# STSPIN32F0A_ESC4.net
KiCad netlist of a schematic drawn in Altium Designer
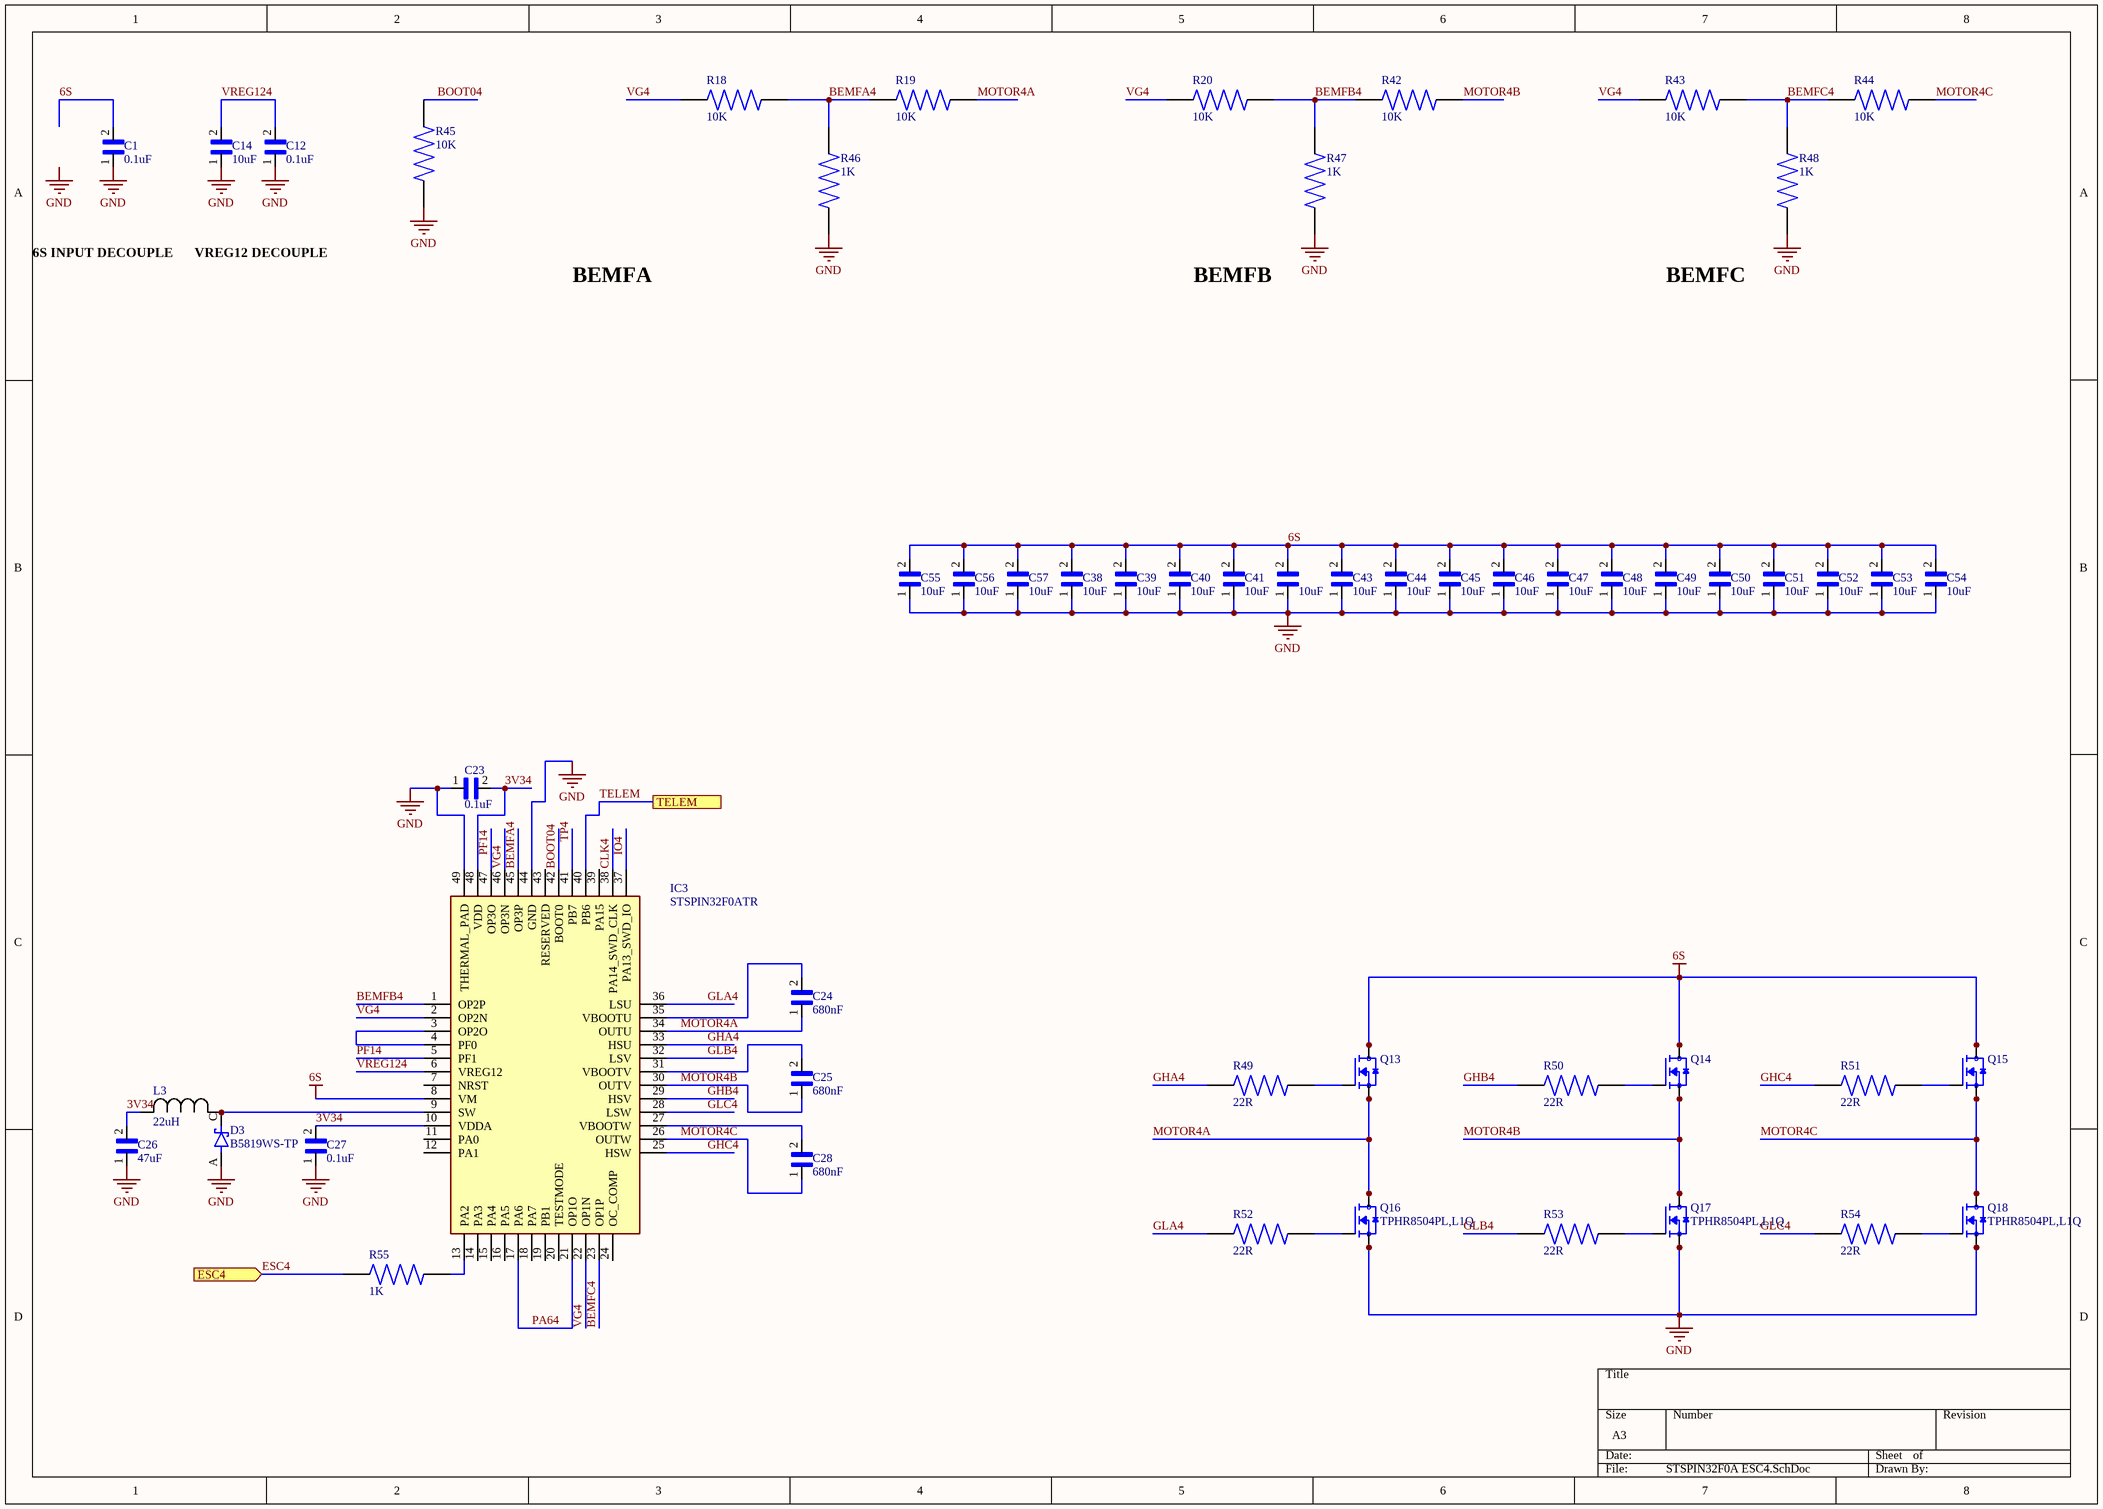
[diagram p0: STSPIN32F0A ESC4.SchDoc]

(export (version "E")
  (design (tool "Eeschema 10.0.6"))
  (components
    (comp (ref "C1")
      (value "0.1uF")
      (footprint "CAPC1005X55N")
      (fields (field (name "MP") "GRM1555C1H222JA01D"))
      (libsource (lib "GRM1555C1H222JA01D") (part "GRM1555C1H222JA01D"))
    )
    (comp (ref "C12")
      (value "0.1uF")
      (footprint "CAPC1005X55N")
      (fields (field (name "MP") "GRM1555C1H222JA01D"))
      (libsource (lib "GRM1555C1H222JA01D") (part "GRM1555C1H222JA01D"))
    )
    (comp (ref "C14")
      (value "10uF")
      (footprint "CAPC1608X90N")
      (description "SMD Capacitor X7R(EIA) with Capacitance: 0.22uF Tol. 5%. Rated Voltage: 25Vdc")
      (fields (field (name "MP") "GRM188R71E224JA88D"))
      (libsource (lib "GRM188R71E224JA88D") (part "GRM188R71E224JA88D"))
    )
    (comp (ref "C23")
      (value "0.1uF")
      (footprint "CAPC1005X55N")
      (fields (field (name "MP") "GRM1555C1H222JA01D"))
      (libsource (lib "") (part "GRM1555C1H222JA01D_1"))
    )
    (comp (ref "C24")
      (value "680nF")
      (footprint "CAPC1005X55N")
      (fields (field (name "MP") "GRM1555C1H222JA01D"))
      (libsource (lib "GRM1555C1H222JA01D") (part "GRM1555C1H222JA01D"))
    )
    (comp (ref "C25")
      (value "680nF")
      (footprint "CAPC1005X55N")
      (fields (field (name "MP") "GRM1555C1H222JA01D"))
      (libsource (lib "GRM1555C1H222JA01D") (part "GRM1555C1H222JA01D"))
    )
    (comp (ref "C26")
      (value "47uF")
      (footprint "CAPC1608X90N")
      (description "SMD Capacitor X7R(EIA) with Capacitance: 0.22uF Tol. 5%. Rated Voltage: 25Vdc")
      (fields (field (name "MP") "GRM188R71E224JA88D"))
      (libsource (lib "GRM188R71E224JA88D") (part "GRM188R71E224JA88D"))
    )
    (comp (ref "C27")
      (value "0.1uF")
      (footprint "CAPC1005X55N")
      (fields (field (name "MP") "GRM1555C1H222JA01D"))
      (libsource (lib "GRM1555C1H222JA01D") (part "GRM1555C1H222JA01D"))
    )
    (comp (ref "C28")
      (value "680nF")
      (footprint "CAPC1005X55N")
      (fields (field (name "MP") "GRM1555C1H222JA01D"))
      (libsource (lib "GRM1555C1H222JA01D") (part "GRM1555C1H222JA01D"))
    )
    (comp (ref "C38")
      (value "10uF")
      (footprint "CAPC3216X190N")
      (description "Ceramic Capacitor")
      (fields (field (name "MP") "GRM31CC80G227ME11K"))
      (libsource (lib "GRM31CC80G227ME11K") (part "GRM31CC80G227ME11K"))
    )
    (comp (ref "C39")
      (value "10uF")
      (footprint "CAPC3216X190N")
      (description "Ceramic Capacitor")
      (fields (field (name "MP") "GRM31CC80G227ME11K"))
      (libsource (lib "GRM31CC80G227ME11K") (part "GRM31CC80G227ME11K"))
    )
    (comp (ref "C40")
      (value "10uF")
      (footprint "CAPC3216X190N")
      (description "Ceramic Capacitor")
      (fields (field (name "MP") "GRM31CC80G227ME11K"))
      (libsource (lib "GRM31CC80G227ME11K") (part "GRM31CC80G227ME11K"))
    )
    (comp (ref "C41")
      (value "10uF")
      (footprint "CAPC3216X190N")
      (description "Ceramic Capacitor")
      (fields (field (name "MP") "GRM31CC80G227ME11K"))
      (libsource (lib "GRM31CC80G227ME11K") (part "GRM31CC80G227ME11K"))
    )
    (comp (ref "C42")
      (value "10uF")
      (footprint "CAPC3216X190N")
      (description "Ceramic Capacitor")
      (fields (field (name "MP") "GRM31CC80G227ME11K"))
      (libsource (lib "GRM31CC80G227ME11K") (part "GRM31CC80G227ME11K"))
    )
    (comp (ref "C43")
      (value "10uF")
      (footprint "CAPC3216X190N")
      (description "Ceramic Capacitor")
      (fields (field (name "MP") "GRM31CC80G227ME11K"))
      (libsource (lib "GRM31CC80G227ME11K") (part "GRM31CC80G227ME11K"))
    )
    (comp (ref "C44")
      (value "10uF")
      (footprint "CAPC3216X190N")
      (description "Ceramic Capacitor")
      (fields (field (name "MP") "GRM31CC80G227ME11K"))
      (libsource (lib "GRM31CC80G227ME11K") (part "GRM31CC80G227ME11K"))
    )
    (comp (ref "C45")
      (value "10uF")
      (footprint "CAPC3216X190N")
      (description "Ceramic Capacitor")
      (fields (field (name "MP") "GRM31CC80G227ME11K"))
      (libsource (lib "GRM31CC80G227ME11K") (part "GRM31CC80G227ME11K"))
    )
    (comp (ref "C46")
      (value "10uF")
      (footprint "CAPC3216X190N")
      (description "Ceramic Capacitor")
      (fields (field (name "MP") "GRM31CC80G227ME11K"))
      (libsource (lib "GRM31CC80G227ME11K") (part "GRM31CC80G227ME11K"))
    )
    (comp (ref "C47")
      (value "10uF")
      (footprint "CAPC3216X190N")
      (description "Ceramic Capacitor")
      (fields (field (name "MP") "GRM31CC80G227ME11K"))
      (libsource (lib "GRM31CC80G227ME11K") (part "GRM31CC80G227ME11K"))
    )
    (comp (ref "C48")
      (value "10uF")
      (footprint "CAPC3216X190N")
      (description "Ceramic Capacitor")
      (fields (field (name "MP") "GRM31CC80G227ME11K"))
      (libsource (lib "GRM31CC80G227ME11K") (part "GRM31CC80G227ME11K"))
    )
    (comp (ref "C49")
      (value "10uF")
      (footprint "CAPC3216X190N")
      (description "Ceramic Capacitor")
      (fields (field (name "MP") "GRM31CC80G227ME11K"))
      (libsource (lib "GRM31CC80G227ME11K") (part "GRM31CC80G227ME11K"))
    )
    (comp (ref "C50")
      (value "10uF")
      (footprint "CAPC3216X190N")
      (description "Ceramic Capacitor")
      (fields (field (name "MP") "GRM31CC80G227ME11K"))
      (libsource (lib "GRM31CC80G227ME11K") (part "GRM31CC80G227ME11K"))
    )
    (comp (ref "C51")
      (value "10uF")
      (footprint "CAPC3216X190N")
      (description "Ceramic Capacitor")
      (fields (field (name "MP") "GRM31CC80G227ME11K"))
      (libsource (lib "GRM31CC80G227ME11K") (part "GRM31CC80G227ME11K"))
    )
    (comp (ref "C52")
      (value "10uF")
      (footprint "CAPC3216X190N")
      (description "Ceramic Capacitor")
      (fields (field (name "MP") "GRM31CC80G227ME11K"))
      (libsource (lib "GRM31CC80G227ME11K") (part "GRM31CC80G227ME11K"))
    )
    (comp (ref "C53")
      (value "10uF")
      (footprint "CAPC3216X190N")
      (description "Ceramic Capacitor")
      (fields (field (name "MP") "GRM31CC80G227ME11K"))
      (libsource (lib "GRM31CC80G227ME11K") (part "GRM31CC80G227ME11K"))
    )
    (comp (ref "C54")
      (value "10uF")
      (footprint "CAPC3216X190N")
      (description "Ceramic Capacitor")
      (fields (field (name "MP") "GRM31CC80G227ME11K"))
      (libsource (lib "GRM31CC80G227ME11K") (part "GRM31CC80G227ME11K"))
    )
    (comp (ref "C55")
      (value "10uF")
      (footprint "CAPC3216X190N")
      (description "Ceramic Capacitor")
      (fields (field (name "MP") "GRM31CC80G227ME11K"))
      (libsource (lib "GRM31CC80G227ME11K") (part "GRM31CC80G227ME11K"))
    )
    (comp (ref "C56")
      (value "10uF")
      (footprint "CAPC3216X190N")
      (description "Ceramic Capacitor")
      (fields (field (name "MP") "GRM31CC80G227ME11K"))
      (libsource (lib "GRM31CC80G227ME11K") (part "GRM31CC80G227ME11K"))
    )
    (comp (ref "C57")
      (value "10uF")
      (footprint "CAPC3216X190N")
      (description "Ceramic Capacitor")
      (fields (field (name "MP") "GRM31CC80G227ME11K"))
      (libsource (lib "GRM31CC80G227ME11K") (part "GRM31CC80G227ME11K"))
    )
    (comp (ref "D3")
      (value "B5819WS-TP")
      (footprint "SOD2512X115N")
      (fields (field (name "MF") "{'manufacturer': u'Micro Commercial Components'}"))
      (libsource (lib "SnapEDA_Library") (part "B5819WS-TP"))
    )
    (comp (ref "IC3")
      (value "STSPIN32F0ATR")
      (footprint "SamacSys:QFN50P700X700X100-49N-D")
      (description "Integrated Circuit")
      (fields (field (name "MOUSER PART NUMBER") "511-STSPIN32F0ATR"))
      (libsource (lib "SamacSys") (part "STSPIN32F0ATR"))
    )
    (comp (ref "L3")
      (value "22uH")
      (footprint "IND_BOURNS_SRN3015")
      (description "No Description Available")
      (fields
        (field (name "MANUFACTURER_PART_NUMBER") "SRN3015-220M")
        (field (name "COPYRIGHT") "Copyright (C) 2022 Ultra Librarian. All rights reserved.")
      )
      (libsource (lib "SRN3015-220M") (part "SRN3015-220M"))
    )
    (comp (ref "Q13")
      (value "TPHR8504PL,L1Q")
      (footprint "TRANS_TPHR8504PL,L1Q")
      (description "N-Channel 40V 150A (Tc) 1W (Ta), 170W (Tc) Surface Mount 8-SOP Advance (5x5)")
      (fields (field (name "MF") "Toshiba Semiconductor"))
      (libsource (lib "TPHR8504PL_L1Q") (part "TPHR8504PL,L1Q"))
    )
    (comp (ref "Q14")
      (value "TPHR8504PL,L1Q")
      (footprint "TRANS_TPHR8504PL,L1Q")
      (description "N-Channel 40V 150A (Tc) 1W (Ta), 170W (Tc) Surface Mount 8-SOP Advance (5x5)")
      (fields (field (name "MF") "Toshiba Semiconductor"))
      (libsource (lib "TPHR8504PL_L1Q") (part "TPHR8504PL,L1Q"))
    )
    (comp (ref "Q15")
      (value "TPHR8504PL,L1Q")
      (footprint "TRANS_TPHR8504PL,L1Q")
      (description "N-Channel 40V 150A (Tc) 1W (Ta), 170W (Tc) Surface Mount 8-SOP Advance (5x5)")
      (fields (field (name "MF") "Toshiba Semiconductor"))
      (libsource (lib "TPHR8504PL_L1Q") (part "TPHR8504PL,L1Q"))
    )
    (comp (ref "Q16")
      (value "TPHR8504PL,L1Q")
      (footprint "TRANS_TPHR8504PL,L1Q")
      (description "N-Channel 40V 150A (Tc) 1W (Ta), 170W (Tc) Surface Mount 8-SOP Advance (5x5)")
      (fields (field (name "MF") "Toshiba Semiconductor"))
      (libsource (lib "TPHR8504PL_L1Q") (part "TPHR8504PL,L1Q"))
    )
    (comp (ref "Q17")
      (value "TPHR8504PL,L1Q")
      (footprint "TRANS_TPHR8504PL,L1Q")
      (description "N-Channel 40V 150A (Tc) 1W (Ta), 170W (Tc) Surface Mount 8-SOP Advance (5x5)")
      (fields (field (name "MF") "Toshiba Semiconductor"))
      (libsource (lib "TPHR8504PL_L1Q") (part "TPHR8504PL,L1Q"))
    )
    (comp (ref "Q18")
      (value "TPHR8504PL,L1Q")
      (footprint "TRANS_TPHR8504PL,L1Q")
      (description "N-Channel 40V 150A (Tc) 1W (Ta), 170W (Tc) Surface Mount 8-SOP Advance (5x5)")
      (fields (field (name "MF") "Toshiba Semiconductor"))
      (libsource (lib "TPHR8504PL_L1Q") (part "TPHR8504PL,L1Q"))
    )
    (comp (ref "R18")
      (value "10K")
      (footprint "RESC1005X37N")
      (fields (field (name "MP") "RE0402BRE07330KL") (field (name "MF") "{'manufacturer': u'Yageo'}"))
      (libsource (lib "SnapEDA_Library") (part "RE0402BRE07330KL"))
    )
    (comp (ref "R19")
      (value "10K")
      (footprint "RESC1005X37N")
      (fields (field (name "MP") "RE0402BRE07330KL") (field (name "MF") "{'manufacturer': u'Yageo'}"))
      (libsource (lib "SnapEDA_Library") (part "RE0402BRE07330KL"))
    )
    (comp (ref "R20")
      (value "10K")
      (footprint "RESC1005X37N")
      (fields (field (name "MP") "RE0402BRE07330KL") (field (name "MF") "{'manufacturer': u'Yageo'}"))
      (libsource (lib "SnapEDA_Library") (part "RE0402BRE07330KL"))
    )
    (comp (ref "R42")
      (value "10K")
      (footprint "RESC1005X37N")
      (fields (field (name "MP") "RE0402BRE07330KL") (field (name "MF") "{'manufacturer': u'Yageo'}"))
      (libsource (lib "SnapEDA_Library") (part "RE0402BRE07330KL"))
    )
    (comp (ref "R43")
      (value "10K")
      (footprint "RESC1005X37N")
      (fields (field (name "MP") "RE0402BRE07330KL") (field (name "MF") "{'manufacturer': u'Yageo'}"))
      (libsource (lib "SnapEDA_Library") (part "RE0402BRE07330KL"))
    )
    (comp (ref "R44")
      (value "10K")
      (footprint "RESC1005X37N")
      (fields (field (name "MP") "RE0402BRE07330KL") (field (name "MF") "{'manufacturer': u'Yageo'}"))
      (libsource (lib "SnapEDA_Library") (part "RE0402BRE07330KL"))
    )
    (comp (ref "R45")
      (value "10K")
      (footprint "RESC1005X37N")
      (fields (field (name "MP") "RE0402BRE07330KL") (field (name "MF") "{'manufacturer': u'Yageo'}"))
      (libsource (lib "SnapEDA_Library") (part "RE0402BRE07330KL"))
    )
    (comp (ref "R46")
      (value "1K")
      (footprint "RESC1005X37N")
      (fields (field (name "MP") "RE0402BRE07330KL") (field (name "MF") "{'manufacturer': u'Yageo'}"))
      (libsource (lib "SnapEDA_Library") (part "RE0402BRE07330KL"))
    )
    (comp (ref "R47")
      (value "1K")
      (footprint "RESC1005X37N")
      (fields (field (name "MP") "RE0402BRE07330KL") (field (name "MF") "{'manufacturer': u'Yageo'}"))
      (libsource (lib "SnapEDA_Library") (part "RE0402BRE07330KL"))
    )
    (comp (ref "R48")
      (value "1K")
      (footprint "RESC1005X37N")
      (fields (field (name "MP") "RE0402BRE07330KL") (field (name "MF") "{'manufacturer': u'Yageo'}"))
      (libsource (lib "SnapEDA_Library") (part "RE0402BRE07330KL"))
    )
    (comp (ref "R49")
      (value "22R")
      (footprint "RESC1005X37N")
      (fields (field (name "MP") "RE0402BRE07330KL") (field (name "MF") "{'manufacturer': u'Yageo'}"))
      (libsource (lib "SnapEDA_Library") (part "RE0402BRE07330KL"))
    )
    (comp (ref "R50")
      (value "22R")
      (footprint "RESC1005X37N")
      (fields (field (name "MP") "RE0402BRE07330KL") (field (name "MF") "{'manufacturer': u'Yageo'}"))
      (libsource (lib "SnapEDA_Library") (part "RE0402BRE07330KL"))
    )
    (comp (ref "R51")
      (value "22R")
      (footprint "RESC1005X37N")
      (fields (field (name "MP") "RE0402BRE07330KL") (field (name "MF") "{'manufacturer': u'Yageo'}"))
      (libsource (lib "SnapEDA_Library") (part "RE0402BRE07330KL"))
    )
    (comp (ref "R52")
      (value "22R")
      (footprint "RESC1005X37N")
      (fields (field (name "MP") "RE0402BRE07330KL") (field (name "MF") "{'manufacturer': u'Yageo'}"))
      (libsource (lib "SnapEDA_Library") (part "RE0402BRE07330KL"))
    )
    (comp (ref "R53")
      (value "22R")
      (footprint "RESC1005X37N")
      (fields (field (name "MP") "RE0402BRE07330KL") (field (name "MF") "{'manufacturer': u'Yageo'}"))
      (libsource (lib "SnapEDA_Library") (part "RE0402BRE07330KL"))
    )
    (comp (ref "R54")
      (value "22R")
      (footprint "RESC1005X37N")
      (fields (field (name "MP") "RE0402BRE07330KL") (field (name "MF") "{'manufacturer': u'Yageo'}"))
      (libsource (lib "SnapEDA_Library") (part "RE0402BRE07330KL"))
    )
    (comp (ref "R55")
      (value "1K")
      (footprint "RESC1005X37N")
      (fields (field (name "MP") "RE0402BRE07330KL") (field (name "MF") "{'manufacturer': u'Yageo'}"))
      (libsource (lib "SnapEDA_Library") (part "RE0402BRE07330KL"))
    )
  )
  (nets
    (net (code "1") (name "/3V34") (class "Default")
      (node (ref "C23") (pin "2") (pinfunction "2_2") (pintype "passive"))
      (node (ref "C26") (pin "2") (pinfunction "2_2") (pintype "passive"))
      (node (ref "C27") (pin "2") (pinfunction "2_2") (pintype "passive"))
      (node (ref "IC3") (pin "10") (pinfunction "VDDA_10") (pintype "passive"))
      (node (ref "IC3") (pin "48") (pinfunction "VDD_48") (pintype "passive"))
      (node (ref "L3") (pin "2") (pinfunction "2_2") (pintype "passive"))
    )
    (net (code "2") (name "/BEMFA4") (class "Default")
      (node (ref "IC3") (pin "45") (pinfunction "OP3P_45") (pintype "passive"))
      (node (ref "R18") (pin "1") (pinfunction "1_1") (pintype "passive"))
      (node (ref "R19") (pin "2") (pinfunction "2_2") (pintype "passive"))
      (node (ref "R46") (pin "1") (pinfunction "1_1") (pintype "passive"))
    )
    (net (code "3") (name "/BEMFB4") (class "Default")
      (node (ref "IC3") (pin "1") (pinfunction "OP2P_1") (pintype "passive"))
      (node (ref "R20") (pin "1") (pinfunction "1_1") (pintype "passive"))
      (node (ref "R42") (pin "2") (pinfunction "2_2") (pintype "passive"))
      (node (ref "R47") (pin "1") (pinfunction "1_1") (pintype "passive"))
    )
    (net (code "4") (name "/BEMFC4") (class "Default")
      (node (ref "IC3") (pin "23") (pinfunction "OP1P_23") (pintype "passive"))
      (node (ref "R43") (pin "1") (pinfunction "1_1") (pintype "passive"))
      (node (ref "R44") (pin "2") (pinfunction "2_2") (pintype "passive"))
      (node (ref "R48") (pin "1") (pinfunction "1_1") (pintype "passive"))
    )
    (net (code "5") (name "/BOOT04") (class "Default")
      (node (ref "IC3") (pin "42") (pinfunction "BOOT0_42") (pintype "passive"))
      (node (ref "R45") (pin "2") (pinfunction "2_2") (pintype "passive"))
    )
    (net (code "6") (name "/CLK4") (class "Default")
      (node (ref "IC3") (pin "38") (pinfunction "PA14_SWD_CLK_38") (pintype "passive"))
    )
    (net (code "7") (name "/ESC4") (class "Default")
      (node (ref "R55") (pin "1") (pinfunction "1_1") (pintype "passive"))
    )
    (net (code "8") (name "/GHA4") (class "Default")
      (node (ref "IC3") (pin "33") (pinfunction "HSU_33") (pintype "passive"))
      (node (ref "R49") (pin "2") (pinfunction "2_2") (pintype "passive"))
    )
    (net (code "9") (name "/GHB4") (class "Default")
      (node (ref "IC3") (pin "29") (pinfunction "HSV_29") (pintype "passive"))
      (node (ref "R50") (pin "2") (pinfunction "2_2") (pintype "passive"))
    )
    (net (code "10") (name "/GHC4") (class "Default")
      (node (ref "IC3") (pin "25") (pinfunction "HSW_25") (pintype "passive"))
      (node (ref "R51") (pin "2") (pinfunction "2_2") (pintype "passive"))
    )
    (net (code "11") (name "/GLA4") (class "Default")
      (node (ref "IC3") (pin "36") (pinfunction "LSU_36") (pintype "passive"))
      (node (ref "R52") (pin "2") (pinfunction "2_2") (pintype "passive"))
    )
    (net (code "12") (name "/GLB4") (class "Default")
      (node (ref "IC3") (pin "32") (pinfunction "LSV_32") (pintype "passive"))
      (node (ref "R53") (pin "2") (pinfunction "2_2") (pintype "passive"))
    )
    (net (code "13") (name "/GLC4") (class "Default")
      (node (ref "IC3") (pin "28") (pinfunction "LSW_28") (pintype "passive"))
      (node (ref "R54") (pin "2") (pinfunction "2_2") (pintype "passive"))
    )
    (net (code "14") (name "/IO4") (class "Default")
      (node (ref "IC3") (pin "37") (pinfunction "PA13_SWD_IO_37") (pintype "passive"))
    )
    (net (code "15") (name "/MOTOR4A") (class "Default")
      (node (ref "C24") (pin "1") (pinfunction "1_1") (pintype "passive"))
      (node (ref "IC3") (pin "34") (pinfunction "OUTU_34") (pintype "passive"))
      (node (ref "Q13") (pin "1") (pinfunction "S_1") (pintype "passive"))
      (node (ref "Q13") (pin "2") (pinfunction "S_2") (pintype "passive"))
      (node (ref "Q13") (pin "3") (pinfunction "S_3") (pintype "passive"))
      (node (ref "Q16") (pin "5") (pinfunction "D_5") (pintype "passive"))
      (node (ref "Q16") (pin "6") (pinfunction "D_6") (pintype "passive"))
      (node (ref "Q16") (pin "7") (pinfunction "D_7") (pintype "passive"))
      (node (ref "Q16") (pin "8") (pinfunction "D_8") (pintype "passive"))
      (node (ref "Q16") (pin "9") (pinfunction "D_9") (pintype "passive"))
      (node (ref "R19") (pin "1") (pinfunction "1_1") (pintype "passive"))
    )
    (net (code "16") (name "/MOTOR4B") (class "Default")
      (node (ref "C25") (pin "1") (pinfunction "1_1") (pintype "passive"))
      (node (ref "IC3") (pin "30") (pinfunction "OUTV_30") (pintype "passive"))
      (node (ref "Q14") (pin "1") (pinfunction "S_1") (pintype "passive"))
      (node (ref "Q14") (pin "2") (pinfunction "S_2") (pintype "passive"))
      (node (ref "Q14") (pin "3") (pinfunction "S_3") (pintype "passive"))
      (node (ref "Q17") (pin "5") (pinfunction "D_5") (pintype "passive"))
      (node (ref "Q17") (pin "6") (pinfunction "D_6") (pintype "passive"))
      (node (ref "Q17") (pin "7") (pinfunction "D_7") (pintype "passive"))
      (node (ref "Q17") (pin "8") (pinfunction "D_8") (pintype "passive"))
      (node (ref "Q17") (pin "9") (pinfunction "D_9") (pintype "passive"))
      (node (ref "R42") (pin "1") (pinfunction "1_1") (pintype "passive"))
    )
    (net (code "17") (name "/MOTOR4C") (class "Default")
      (node (ref "C28") (pin "1") (pinfunction "1_1") (pintype "passive"))
      (node (ref "IC3") (pin "26") (pinfunction "OUTW_26") (pintype "passive"))
      (node (ref "Q15") (pin "1") (pinfunction "S_1") (pintype "passive"))
      (node (ref "Q15") (pin "2") (pinfunction "S_2") (pintype "passive"))
      (node (ref "Q15") (pin "3") (pinfunction "S_3") (pintype "passive"))
      (node (ref "Q18") (pin "5") (pinfunction "D_5") (pintype "passive"))
      (node (ref "Q18") (pin "6") (pinfunction "D_6") (pintype "passive"))
      (node (ref "Q18") (pin "7") (pinfunction "D_7") (pintype "passive"))
      (node (ref "Q18") (pin "8") (pinfunction "D_8") (pintype "passive"))
      (node (ref "Q18") (pin "9") (pinfunction "D_9") (pintype "passive"))
      (node (ref "R44") (pin "1") (pinfunction "1_1") (pintype "passive"))
    )
    (net (code "18") (name "/PA64") (class "Default")
      (node (ref "IC3") (pin "17") (pinfunction "PA6_17") (pintype "passive"))
      (node (ref "IC3") (pin "21") (pinfunction "OP1O_21") (pintype "passive"))
    )
    (net (code "19") (name "/PF14") (class "Default")
      (node (ref "IC3") (pin "47") (pinfunction "OP3O_47") (pintype "passive"))
      (node (ref "IC3") (pin "5") (pinfunction "PF1_5") (pintype "passive"))
    )
    (net (code "20") (name "/TELEM") (class "Default")
      (node (ref "IC3") (pin "40") (pinfunction "PB6_40") (pintype "passive"))
    )
    (net (code "21") (name "/TP4") (class "Default")
      (node (ref "IC3") (pin "41") (pinfunction "PB7_41") (pintype "passive"))
    )
    (net (code "22") (name "/VG4") (class "Default")
      (node (ref "IC3") (pin "2") (pinfunction "OP2N_2") (pintype "passive"))
      (node (ref "IC3") (pin "22") (pinfunction "OP1N_22") (pintype "passive"))
      (node (ref "IC3") (pin "46") (pinfunction "OP3N_46") (pintype "passive"))
      (node (ref "R18") (pin "2") (pinfunction "2_2") (pintype "passive"))
      (node (ref "R20") (pin "2") (pinfunction "2_2") (pintype "passive"))
      (node (ref "R43") (pin "2") (pinfunction "2_2") (pintype "passive"))
    )
    (net (code "23") (name "/VREG124") (class "Default")
      (node (ref "C12") (pin "2") (pinfunction "2_2") (pintype "passive"))
      (node (ref "C14") (pin "2") (pinfunction "2_2") (pintype "passive"))
      (node (ref "IC3") (pin "6") (pinfunction "VREG12_6") (pintype "passive"))
    )
    (net (code "24") (name "6S") (class "Default")
      (node (ref "C1") (pin "2") (pinfunction "2_2") (pintype "passive"))
      (node (ref "C38") (pin "2") (pinfunction "2_2") (pintype "passive"))
      (node (ref "C39") (pin "2") (pinfunction "2_2") (pintype "passive"))
      (node (ref "C40") (pin "2") (pinfunction "2_2") (pintype "passive"))
      (node (ref "C41") (pin "2") (pinfunction "2_2") (pintype "passive"))
      (node (ref "C42") (pin "2") (pinfunction "2_2") (pintype "passive"))
      (node (ref "C43") (pin "2") (pinfunction "2_2") (pintype "passive"))
      (node (ref "C44") (pin "2") (pinfunction "2_2") (pintype "passive"))
      (node (ref "C45") (pin "2") (pinfunction "2_2") (pintype "passive"))
      (node (ref "C46") (pin "2") (pinfunction "2_2") (pintype "passive"))
      (node (ref "C47") (pin "2") (pinfunction "2_2") (pintype "passive"))
      (node (ref "C48") (pin "2") (pinfunction "2_2") (pintype "passive"))
      (node (ref "C49") (pin "2") (pinfunction "2_2") (pintype "passive"))
      (node (ref "C50") (pin "2") (pinfunction "2_2") (pintype "passive"))
      (node (ref "C51") (pin "2") (pinfunction "2_2") (pintype "passive"))
      (node (ref "C52") (pin "2") (pinfunction "2_2") (pintype "passive"))
      (node (ref "C53") (pin "2") (pinfunction "2_2") (pintype "passive"))
      (node (ref "C54") (pin "2") (pinfunction "2_2") (pintype "passive"))
      (node (ref "C55") (pin "2") (pinfunction "2_2") (pintype "passive"))
      (node (ref "C56") (pin "2") (pinfunction "2_2") (pintype "passive"))
      (node (ref "C57") (pin "2") (pinfunction "2_2") (pintype "passive"))
      (node (ref "IC3") (pin "8") (pinfunction "VM_8") (pintype "passive"))
      (node (ref "Q13") (pin "5") (pinfunction "D_5") (pintype "passive"))
      (node (ref "Q13") (pin "6") (pinfunction "D_6") (pintype "passive"))
      (node (ref "Q13") (pin "7") (pinfunction "D_7") (pintype "passive"))
      (node (ref "Q13") (pin "8") (pinfunction "D_8") (pintype "passive"))
      (node (ref "Q13") (pin "9") (pinfunction "D_9") (pintype "passive"))
      (node (ref "Q14") (pin "5") (pinfunction "D_5") (pintype "passive"))
      (node (ref "Q14") (pin "6") (pinfunction "D_6") (pintype "passive"))
      (node (ref "Q14") (pin "7") (pinfunction "D_7") (pintype "passive"))
      (node (ref "Q14") (pin "8") (pinfunction "D_8") (pintype "passive"))
      (node (ref "Q14") (pin "9") (pinfunction "D_9") (pintype "passive"))
      (node (ref "Q15") (pin "5") (pinfunction "D_5") (pintype "passive"))
      (node (ref "Q15") (pin "6") (pinfunction "D_6") (pintype "passive"))
      (node (ref "Q15") (pin "7") (pinfunction "D_7") (pintype "passive"))
      (node (ref "Q15") (pin "8") (pinfunction "D_8") (pintype "passive"))
      (node (ref "Q15") (pin "9") (pinfunction "D_9") (pintype "passive"))
    )
    (net (code "25") (name "GND") (class "Default")
      (node (ref "C1") (pin "1") (pinfunction "1_1") (pintype "passive"))
      (node (ref "C12") (pin "1") (pinfunction "1_1") (pintype "passive"))
      (node (ref "C14") (pin "1") (pinfunction "1_1") (pintype "passive"))
      (node (ref "C23") (pin "1") (pinfunction "1_1") (pintype "passive"))
      (node (ref "C26") (pin "1") (pinfunction "1_1") (pintype "passive"))
      (node (ref "C27") (pin "1") (pinfunction "1_1") (pintype "passive"))
      (node (ref "C38") (pin "1") (pinfunction "1_1") (pintype "passive"))
      (node (ref "C39") (pin "1") (pinfunction "1_1") (pintype "passive"))
      (node (ref "C40") (pin "1") (pinfunction "1_1") (pintype "passive"))
      (node (ref "C41") (pin "1") (pinfunction "1_1") (pintype "passive"))
      (node (ref "C42") (pin "1") (pinfunction "1_1") (pintype "passive"))
      (node (ref "C43") (pin "1") (pinfunction "1_1") (pintype "passive"))
      (node (ref "C44") (pin "1") (pinfunction "1_1") (pintype "passive"))
      (node (ref "C45") (pin "1") (pinfunction "1_1") (pintype "passive"))
      (node (ref "C46") (pin "1") (pinfunction "1_1") (pintype "passive"))
      (node (ref "C47") (pin "1") (pinfunction "1_1") (pintype "passive"))
      (node (ref "C48") (pin "1") (pinfunction "1_1") (pintype "passive"))
      (node (ref "C49") (pin "1") (pinfunction "1_1") (pintype "passive"))
      (node (ref "C50") (pin "1") (pinfunction "1_1") (pintype "passive"))
      (node (ref "C51") (pin "1") (pinfunction "1_1") (pintype "passive"))
      (node (ref "C52") (pin "1") (pinfunction "1_1") (pintype "passive"))
      (node (ref "C53") (pin "1") (pinfunction "1_1") (pintype "passive"))
      (node (ref "C54") (pin "1") (pinfunction "1_1") (pintype "passive"))
      (node (ref "C55") (pin "1") (pinfunction "1_1") (pintype "passive"))
      (node (ref "C56") (pin "1") (pinfunction "1_1") (pintype "passive"))
      (node (ref "C57") (pin "1") (pinfunction "1_1") (pintype "passive"))
      (node (ref "D3") (pin "A") (pinfunction "A_A") (pintype "passive"))
      (node (ref "IC3") (pin "44") (pinfunction "GND_44") (pintype "passive"))
      (node (ref "IC3") (pin "49") (pinfunction "THERMAL_PAD_49") (pintype "passive"))
      (node (ref "Q16") (pin "1") (pinfunction "S_1") (pintype "passive"))
      (node (ref "Q16") (pin "2") (pinfunction "S_2") (pintype "passive"))
      (node (ref "Q16") (pin "3") (pinfunction "S_3") (pintype "passive"))
      (node (ref "Q17") (pin "1") (pinfunction "S_1") (pintype "passive"))
      (node (ref "Q17") (pin "2") (pinfunction "S_2") (pintype "passive"))
      (node (ref "Q17") (pin "3") (pinfunction "S_3") (pintype "passive"))
      (node (ref "Q18") (pin "1") (pinfunction "S_1") (pintype "passive"))
      (node (ref "Q18") (pin "2") (pinfunction "S_2") (pintype "passive"))
      (node (ref "Q18") (pin "3") (pinfunction "S_3") (pintype "passive"))
      (node (ref "R45") (pin "1") (pinfunction "1_1") (pintype "passive"))
      (node (ref "R46") (pin "2") (pinfunction "2_2") (pintype "passive"))
      (node (ref "R47") (pin "2") (pinfunction "2_2") (pintype "passive"))
      (node (ref "R48") (pin "2") (pinfunction "2_2") (pintype "passive"))
    )
    (net (code "26") (name "Net-(D3-K)") (class "Default")
      (node (ref "D3") (pin "C") (pinfunction "K_C") (pintype "passive"))
      (node (ref "IC3") (pin "9") (pinfunction "SW_9") (pintype "passive"))
      (node (ref "L3") (pin "1") (pinfunction "1_1") (pintype "passive"))
    )
    (net (code "27") (name "Net-(IC3-OP2O)") (class "Default")
      (node (ref "IC3") (pin "3") (pinfunction "OP2O_3") (pintype "passive"))
      (node (ref "IC3") (pin "4") (pinfunction "PF0_4") (pintype "passive"))
    )
    (net (code "28") (name "Net-(IC3-PA2)") (class "Default")
      (node (ref "IC3") (pin "13") (pinfunction "PA2_13") (pintype "passive"))
      (node (ref "R55") (pin "2") (pinfunction "2_2") (pintype "passive"))
    )
    (net (code "29") (name "Net-(IC3-VBOOTU)") (class "Default")
      (node (ref "C24") (pin "2") (pinfunction "2_2") (pintype "passive"))
      (node (ref "IC3") (pin "35") (pinfunction "VBOOTU_35") (pintype "passive"))
    )
    (net (code "30") (name "Net-(IC3-VBOOTV)") (class "Default")
      (node (ref "C25") (pin "2") (pinfunction "2_2") (pintype "passive"))
      (node (ref "IC3") (pin "31") (pinfunction "VBOOTV_31") (pintype "passive"))
    )
    (net (code "31") (name "Net-(IC3-VBOOTW)") (class "Default")
      (node (ref "C28") (pin "2") (pinfunction "2_2") (pintype "passive"))
      (node (ref "IC3") (pin "27") (pinfunction "VBOOTW_27") (pintype "passive"))
    )
    (net (code "32") (name "Net-(Q13-G)") (class "Default")
      (node (ref "Q13") (pin "4") (pinfunction "G_4") (pintype "passive"))
      (node (ref "R49") (pin "1") (pinfunction "1_1") (pintype "passive"))
    )
    (net (code "33") (name "Net-(Q14-G)") (class "Default")
      (node (ref "Q14") (pin "4") (pinfunction "G_4") (pintype "passive"))
      (node (ref "R50") (pin "1") (pinfunction "1_1") (pintype "passive"))
    )
    (net (code "34") (name "Net-(Q15-G)") (class "Default")
      (node (ref "Q15") (pin "4") (pinfunction "G_4") (pintype "passive"))
      (node (ref "R51") (pin "1") (pinfunction "1_1") (pintype "passive"))
    )
    (net (code "35") (name "Net-(Q16-G)") (class "Default")
      (node (ref "Q16") (pin "4") (pinfunction "G_4") (pintype "passive"))
      (node (ref "R52") (pin "1") (pinfunction "1_1") (pintype "passive"))
    )
    (net (code "36") (name "Net-(Q17-G)") (class "Default")
      (node (ref "Q17") (pin "4") (pinfunction "G_4") (pintype "passive"))
      (node (ref "R53") (pin "1") (pinfunction "1_1") (pintype "passive"))
    )
    (net (code "37") (name "Net-(Q18-G)") (class "Default")
      (node (ref "Q18") (pin "4") (pinfunction "G_4") (pintype "passive"))
      (node (ref "R54") (pin "1") (pinfunction "1_1") (pintype "passive"))
    )
    (net (code "38") (name "unconnected-(IC3-NRST-Pad7)") (class "Default")
      (node (ref "IC3") (pin "7") (pinfunction "NRST_7") (pintype "passive"))
    )
    (net (code "39") (name "unconnected-(IC3-OC_COMP-Pad24)") (class "Default")
      (node (ref "IC3") (pin "24") (pinfunction "OC_COMP_24") (pintype "passive"))
    )
    (net (code "40") (name "unconnected-(IC3-PA0-Pad11)") (class "Default")
      (node (ref "IC3") (pin "11") (pinfunction "PA0_11") (pintype "passive"))
    )
    (net (code "41") (name "unconnected-(IC3-PA1-Pad12)") (class "Default")
      (node (ref "IC3") (pin "12") (pinfunction "PA1_12") (pintype "passive"))
    )
    (net (code "42") (name "unconnected-(IC3-PA3-Pad14)") (class "Default")
      (node (ref "IC3") (pin "14") (pinfunction "PA3_14") (pintype "passive"))
    )
    (net (code "43") (name "unconnected-(IC3-PA4-Pad15)") (class "Default")
      (node (ref "IC3") (pin "15") (pinfunction "PA4_15") (pintype "passive"))
    )
    (net (code "44") (name "unconnected-(IC3-PA5-Pad16)") (class "Default")
      (node (ref "IC3") (pin "16") (pinfunction "PA5_16") (pintype "passive"))
    )
    (net (code "45") (name "unconnected-(IC3-PA7-Pad18)") (class "Default")
      (node (ref "IC3") (pin "18") (pinfunction "PA7_18") (pintype "passive"))
    )
    (net (code "46") (name "unconnected-(IC3-PA15-Pad39)") (class "Default")
      (node (ref "IC3") (pin "39") (pinfunction "PA15_39") (pintype "passive"))
    )
    (net (code "47") (name "unconnected-(IC3-PB1-Pad19)") (class "Default")
      (node (ref "IC3") (pin "19") (pinfunction "PB1_19") (pintype "passive"))
    )
    (net (code "48") (name "unconnected-(IC3-RESERVED-Pad43)") (class "Default")
      (node (ref "IC3") (pin "43") (pinfunction "RESERVED_43") (pintype "passive"))
    )
    (net (code "49") (name "unconnected-(IC3-TESTMODE-Pad20)") (class "Default")
      (node (ref "IC3") (pin "20") (pinfunction "TESTMODE_20") (pintype "passive"))
    )
  )
)
